# Power_onboard.net
KiCad netlist of a schematic drawn in Altium Designer
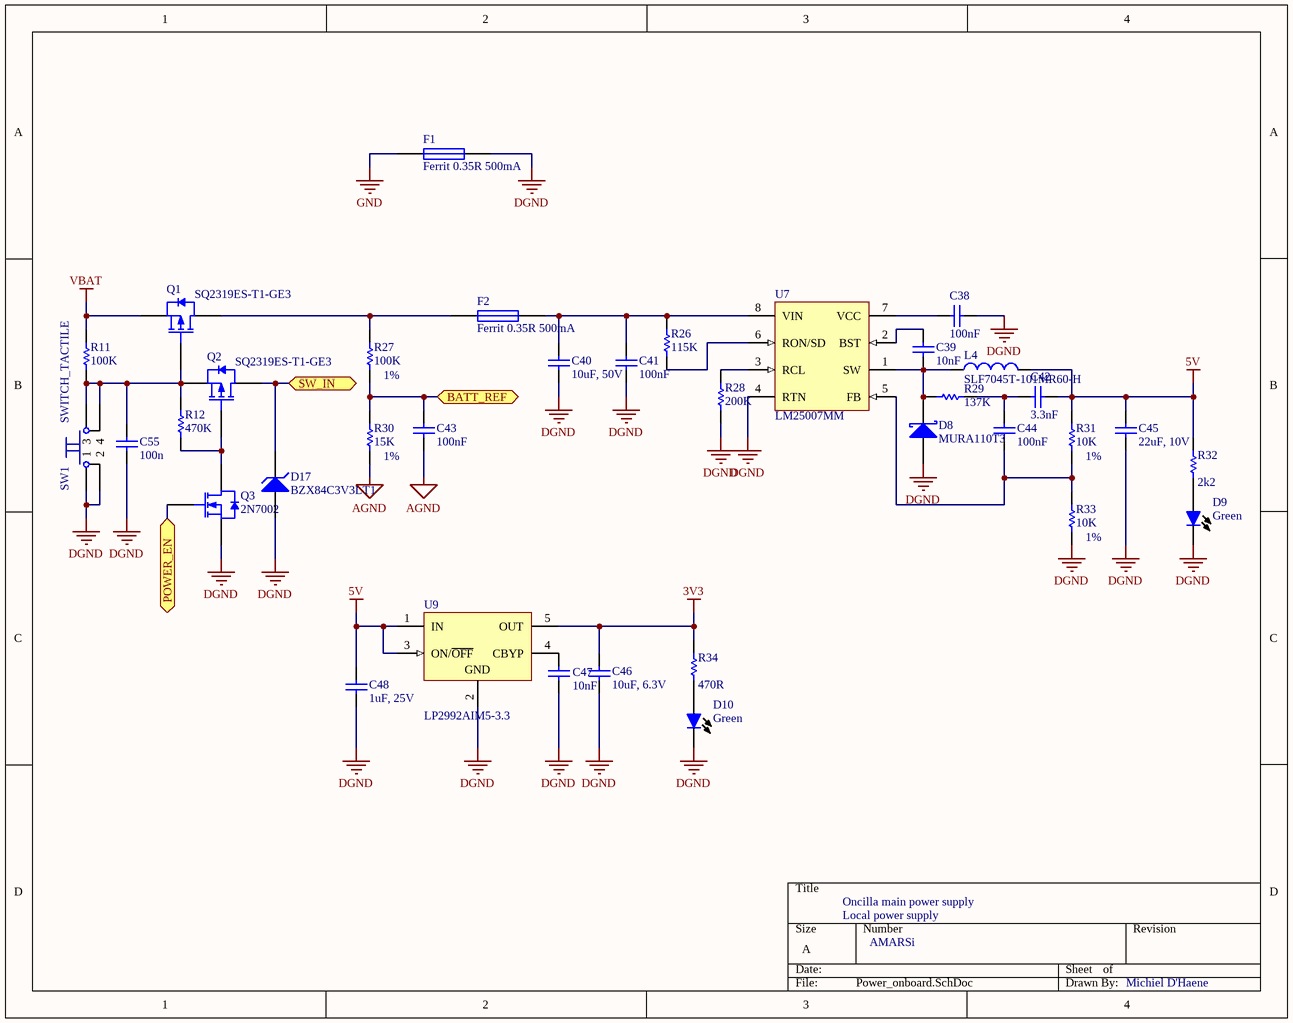
[diagram p0: Power_onboard.SchDoc]

(export (version "E")
  (design (tool "Eeschema 10.0.6"))
  (components
    (comp (ref "C38")
      (value "100nF")
      (footprint "CAPC1608L")
      (description "Capacitor (Semiconductor SIM Model)")
      (fields (field (name "PUBLISHER") "Altium Limited"))
      (libsource (lib "Miscellaneous Devices") (part "Cap Semi"))
    )
    (comp (ref "C39")
      (value "10nF")
      (footprint "CAPC1608L")
      (description "Capacitor (Semiconductor SIM Model)")
      (fields (field (name "PUBLISHER") "Altium Limited"))
      (libsource (lib "Miscellaneous Devices") (part "Cap Semi"))
    )
    (comp (ref "C40")
      (value "10uF, 50V")
      (footprint "CAPC3216L")
      (description "Capacitor (Semiconductor SIM Model)")
      (fields (field (name "PUBLISHER") "Altium Limited"))
      (libsource (lib "Miscellaneous Devices") (part "Cap Semi"))
    )
    (comp (ref "C41")
      (value "100nF")
      (footprint "CAPC1608L")
      (description "Capacitor (Semiconductor SIM Model)")
      (fields (field (name "PUBLISHER") "Altium Limited"))
      (libsource (lib "Miscellaneous Devices") (part "Cap Semi"))
    )
    (comp (ref "C42")
      (value "3.3nF")
      (footprint "CAPC1608L")
      (description "Capacitor (Semiconductor SIM Model)")
      (fields (field (name "PUBLISHER") "Altium Limited"))
      (libsource (lib "Miscellaneous Devices") (part "Cap Semi"))
    )
    (comp (ref "C43")
      (value "100nF")
      (footprint "CAPC1608L")
      (description "Capacitor (Semiconductor SIM Model)")
      (fields (field (name "PUBLISHER") "Altium Limited"))
      (libsource (lib "Miscellaneous Devices") (part "Cap Semi"))
    )
    (comp (ref "C44")
      (value "100nF")
      (footprint "CAPC1608L")
      (description "Capacitor (Semiconductor SIM Model)")
      (fields (field (name "Comment") "22nF") (field (name "PUBLISHER") "Altium Limited"))
      (libsource (lib "Miscellaneous Devices") (part "Cap Semi"))
    )
    (comp (ref "C45")
      (value "22uF, 10V")
      (footprint "CAPC3216L")
      (description "Capacitor (Semiconductor SIM Model)")
      (fields (field (name "PUBLISHER") "Altium Limited"))
      (libsource (lib "Miscellaneous Devices") (part "Cap Semi"))
    )
    (comp (ref "C46")
      (value "10uF, 6.3V")
      (footprint "CAPC1608L")
      (description "Capacitor (Semiconductor SIM Model)")
      (fields (field (name "PUBLISHER") "Altium Limited"))
      (libsource (lib "Miscellaneous Devices") (part "Cap Semi"))
    )
    (comp (ref "C47")
      (value "10nF")
      (footprint "CAPC1608L")
      (description "Capacitor (Semiconductor SIM Model)")
      (fields (field (name "PUBLISHER") "Altium Limited"))
      (libsource (lib "Miscellaneous Devices") (part "Cap Semi"))
    )
    (comp (ref "C48")
      (value "1uF, 25V")
      (footprint "CAPC1608L")
      (description "Capacitor (Semiconductor SIM Model)")
      (fields (field (name "PUBLISHER") "Altium Limited"))
      (libsource (lib "Miscellaneous Devices") (part "Cap Semi"))
    )
    (comp (ref "C55")
      (value "100n")
      (footprint "CAPC1608L")
      (description "Capacitor (Semiconductor SIM Model)")
      (fields (field (name "PUBLISHER") "Altium Limited"))
      (libsource (lib "Miscellaneous Devices") (part "Cap Semi"))
    )
    (comp (ref "D8")
      (value "MURA110T3")
      (footprint "SMA")
      (description "Schottky Rectifier")
      (fields (field (name "PUBLISHER") "Altium Limited"))
      (libsource (lib "IR Rectifier - Schottky") (part "10MQ060N"))
    )
    (comp (ref "D9")
      (value "LED Green")
      (footprint "CD1608-0603")
      (description "LED")
      (fields (field (name "COLOR") "Green"))
      (libsource (lib "Roombots") (part "LED"))
    )
    (comp (ref "D10")
      (value "LED Green")
      (footprint "CD1608-0603")
      (description "LED")
      (fields (field (name "COLOR") "Green"))
      (libsource (lib "Roombots") (part "LED"))
    )
    (comp (ref "D17")
      (value "BZX84C3V3LT1")
      (footprint "318-07")
      (description "Zener Voltage Regulator Diode")
      (fields (field (name "PUBLISHER") "Altium Limited"))
      (libsource (lib "Motorola Discrete Diode") (part "BZX84C3V3LT1"))
    )
    (comp (ref "F1")
      (value "Ferrit 0.35R 500mA")
      (footprint "RESC1608L")
      (description "Ferrit Bead")
      (fields (field (name "PUBLISHER") "Altium Limited"))
      (libsource (lib "Miscellaneous Devices") (part "Fuse 1"))
    )
    (comp (ref "F2")
      (value "Ferrit 0.35R 500mA")
      (footprint "RESC1608L")
      (description "Ferrit Bead")
      (fields (field (name "PUBLISHER") "Altium Limited"))
      (libsource (lib "Miscellaneous Devices") (part "Fuse 1"))
    )
    (comp (ref "L4")
      (value "SLF7045T-101MR60-H")
      (footprint "SLF7045T")
      (libsource (lib "New_library") (part "Inductor"))
    )
    (comp (ref "Q1")
      (value "SQ2319ES-T1-GE3")
      (footprint "SOT23_N")
      (description "P-channel Enhancement Mode Vertical D-MOSFET")
      (fields (field (name "PUBLISHER") "Altium Limited"))
      (libsource (lib "Philips Discrete MOSFET - Low Power") (part "BSS84"))
    )
    (comp (ref "Q2")
      (value "SQ2319ES-T1-GE3")
      (footprint "SOT23_N")
      (description "P-channel Enhancement Mode Vertical D-MOSFET")
      (fields (field (name "PUBLISHER") "Altium Limited"))
      (libsource (lib "Philips Discrete MOSFET - Low Power") (part "BSS84"))
    )
    (comp (ref "Q3")
      (value "2N7002")
      (footprint "SOT23_N")
      (description "N-channel Enhancement Mode Field-effect Transistor")
      (fields (field (name "PUBLISHER") "Altium Limited"))
      (libsource (lib "Philips Discrete MOSFET - Low Power") (part "BST82"))
    )
    (comp (ref "R11")
      (value "100K")
      (footprint "RESC1608L")
      (description "Semiconductor Resistor")
      (fields (field (name "Comment") "100k") (field (name "PUBLISHER") "Altium Limited"))
      (libsource (lib "Miscellaneous Devices") (part "Res Semi"))
    )
    (comp (ref "R12")
      (value "470K")
      (footprint "RESC1608L")
      (description "Semiconductor Resistor")
      (fields (field (name "Comment") "100k") (field (name "PUBLISHER") "Altium Limited"))
      (libsource (lib "Miscellaneous Devices") (part "Res Semi"))
    )
    (comp (ref "R26")
      (value "115K")
      (footprint "RESC1608L")
      (description "Semiconductor Resistor")
      (fields (field (name "Comment") "115k") (field (name "PUBLISHER") "Altium Limited"))
      (libsource (lib "Miscellaneous Devices") (part "Res Semi"))
    )
    (comp (ref "R27")
      (value "100K")
      (footprint "RESC1608L")
      (description "Semiconductor Resistor")
      (fields
        (field (name "PRECISION") "1%")
        (field (name "Comment") "100k, 1%")
        (field (name "PUBLISHER") "Altium Limited")
      )
      (libsource (lib "Miscellaneous Devices") (part "Res Semi"))
    )
    (comp (ref "R28")
      (value "200K")
      (footprint "RESC1608L")
      (description "Semiconductor Resistor")
      (fields (field (name "Comment") "200k") (field (name "PUBLISHER") "Altium Limited"))
      (libsource (lib "Miscellaneous Devices") (part "Res Semi"))
    )
    (comp (ref "R29")
      (value "137K")
      (footprint "RESC1608L")
      (description "Semiconductor Resistor")
      (fields (field (name "Comment") "138k") (field (name "PUBLISHER") "Altium Limited"))
      (libsource (lib "Miscellaneous Devices") (part "Res Semi"))
    )
    (comp (ref "R30")
      (value "15K")
      (footprint "RESC1608L")
      (description "Semiconductor Resistor")
      (fields
        (field (name "PRECISION") "1%")
        (field (name "Comment") "15k, 1%")
        (field (name "PUBLISHER") "Altium Limited")
      )
      (libsource (lib "Miscellaneous Devices") (part "Res Semi"))
    )
    (comp (ref "R31")
      (value "10K")
      (footprint "RESC1608L")
      (description "Semiconductor Resistor")
      (fields
        (field (name "PRECISION") "1%")
        (field (name "Comment") "10k, 1%")
        (field (name "PUBLISHER") "Altium Limited")
      )
      (libsource (lib "Miscellaneous Devices") (part "Res Semi"))
    )
    (comp (ref "R32")
      (value "2k2")
      (footprint "RESC1608L")
      (description "Semiconductor Resistor")
      (fields (field (name "PUBLISHER") "Altium Limited"))
      (libsource (lib "Miscellaneous Devices") (part "Res Semi"))
    )
    (comp (ref "R33")
      (value "10K")
      (footprint "RESC1608L")
      (description "Semiconductor Resistor")
      (fields
        (field (name "PRECISION") "1%")
        (field (name "Comment") "10k, 1%")
        (field (name "PUBLISHER") "Altium Limited")
      )
      (libsource (lib "Miscellaneous Devices") (part "Res Semi"))
    )
    (comp (ref "R34")
      (value "470R")
      (footprint "RESC1608L")
      (description "Semiconductor Resistor")
      (fields (field (name "PUBLISHER") "Altium Limited"))
      (libsource (lib "Miscellaneous Devices") (part "Res Semi"))
    )
    (comp (ref "SW1")
      (value "SWITCH_TACTILE")
      (footprint "TACTILE_SWITCH")
      (libsource (lib "New_library") (part "SWITCH_TACTILE"))
    )
    (comp (ref "U7")
      (value "LM25007MM")
      (footprint "MUA08A_N")
      (description "42V, 0.5A Step-Down Switching Regulator")
      (fields
        (field (name "MANUFACTURER") "National Semiconductor")
        (field (name "DIGIKEYPARTNUMBER") "LM25007MMCT-ND")
        (field (name "PUBLISHER") "Altium Limited")
      )
      (libsource (lib "NSC MiscPower") (part "LM25007MM"))
    )
    (comp (ref "U9")
      (value "LP2992AIM5-3.3")
      (footprint "MF05A_N")
      (description "Micropower 250 mA Low-Noise Ultra Low-Dropout Regulator in SOT-23 and LLP Packages")
      (fields
        (field (name "PARTNUMBER") "LP2992AIM5-5.0")
        (field (name "MANUFACTURER") "National Semiconductor")
        (field (name "PUBLISHER") "Altium Limited")
      )
      (libsource (lib "NSC LDO") (part "LP2992AIM5-5.0"))
    )
  )
  (nets
    (net (code "1") (name "/BATT_REF") (class "Default")
      (node (ref "C43") (pin "2") (pinfunction "2_2") (pintype "passive"))
      (node (ref "R27") (pin "1") (pinfunction "1_1") (pintype "passive"))
      (node (ref "R30") (pin "2") (pinfunction "2_2") (pintype "passive"))
    )
    (net (code "2") (name "/POWER_EN") (class "Default")
      (node (ref "Q3") (pin "1") (pinfunction "G_1") (pintype "passive"))
    )
    (net (code "3") (name "/SW_IN") (class "Default")
      (node (ref "D17") (pin "3") (pinfunction "K_3") (pintype "passive"))
      (node (ref "Q2") (pin "3") (pinfunction "D_3") (pintype "passive"))
    )
    (net (code "4") (name "3V3") (class "Default")
      (node (ref "C46") (pin "2") (pinfunction "2_2") (pintype "passive"))
      (node (ref "R34") (pin "2") (pinfunction "2_2") (pintype "passive"))
      (node (ref "U9") (pin "5") (pinfunction "OUT_5") (pintype "power_in"))
    )
    (net (code "5") (name "5V") (class "Default")
      (node (ref "C42") (pin "2") (pinfunction "2_2") (pintype "passive"))
      (node (ref "C45") (pin "2") (pinfunction "2_2") (pintype "passive"))
      (node (ref "C48") (pin "2") (pinfunction "2_2") (pintype "passive"))
      (node (ref "L4") (pin "2") (pinfunction "2_2") (pintype "passive"))
      (node (ref "R31") (pin "2") (pinfunction "2_2") (pintype "passive"))
      (node (ref "R32") (pin "2") (pinfunction "2_2") (pintype "passive"))
      (node (ref "U9") (pin "1") (pinfunction "IN_1") (pintype "power_in"))
      (node (ref "U9") (pin "3") (pinfunction "ON/~{OFF}_3") (pintype "input"))
    )
    (net (code "6") (name "AGND") (class "Default")
      (node (ref "C43") (pin "1") (pinfunction "1_1") (pintype "passive"))
      (node (ref "R30") (pin "1") (pinfunction "1_1") (pintype "passive"))
    )
    (net (code "7") (name "DGND") (class "Default")
      (node (ref "C38") (pin "1") (pinfunction "1_1") (pintype "passive"))
      (node (ref "C40") (pin "1") (pinfunction "1_1") (pintype "passive"))
      (node (ref "C41") (pin "1") (pinfunction "1_1") (pintype "passive"))
      (node (ref "C45") (pin "1") (pinfunction "1_1") (pintype "passive"))
      (node (ref "C46") (pin "1") (pinfunction "1_1") (pintype "passive"))
      (node (ref "C47") (pin "1") (pinfunction "1_1") (pintype "passive"))
      (node (ref "C48") (pin "1") (pinfunction "1_1") (pintype "passive"))
      (node (ref "C55") (pin "1") (pinfunction "1_1") (pintype "passive"))
      (node (ref "D10") (pin "2") (pinfunction "C_2") (pintype "passive"))
      (node (ref "D17") (pin "1") (pinfunction "A_1") (pintype "passive"))
      (node (ref "D8") (pin "1") (pinfunction "A_1") (pintype "passive"))
      (node (ref "D9") (pin "2") (pinfunction "C_2") (pintype "passive"))
      (node (ref "F1") (pin "2") (pinfunction "2_2") (pintype "passive"))
      (node (ref "Q3") (pin "2") (pinfunction "S_2") (pintype "passive"))
      (node (ref "R28") (pin "1") (pinfunction "1_1") (pintype "passive"))
      (node (ref "R33") (pin "1") (pinfunction "1_1") (pintype "passive"))
      (node (ref "SW1") (pin "1") (pinfunction "1_1") (pintype "passive"))
      (node (ref "SW1") (pin "2") (pinfunction "2_2") (pintype "passive"))
      (node (ref "U7") (pin "4") (pinfunction "RTN_4") (pintype "power_in"))
      (node (ref "U9") (pin "2") (pinfunction "GND_2") (pintype "power_in"))
    )
    (net (code "8") (name "GND") (class "Default")
      (node (ref "F1") (pin "1") (pinfunction "1_1") (pintype "passive"))
    )
    (net (code "9") (name "Net-(C42-Pad1)") (class "Default")
      (node (ref "C42") (pin "1") (pinfunction "1_1") (pintype "passive"))
      (node (ref "C44") (pin "2") (pinfunction "2_2") (pintype "passive"))
      (node (ref "R29") (pin "1") (pinfunction "1_1") (pintype "passive"))
    )
    (net (code "10") (name "Net-(D8-K)") (class "Default")
      (node (ref "C39") (pin "1") (pinfunction "1_1") (pintype "passive"))
      (node (ref "D8") (pin "2") (pinfunction "K_2") (pintype "passive"))
      (node (ref "L4") (pin "1") (pinfunction "1_1") (pintype "passive"))
      (node (ref "R29") (pin "2") (pinfunction "2_2") (pintype "passive"))
      (node (ref "U7") (pin "1") (pinfunction "SW_1") (pintype "power_in"))
    )
    (net (code "11") (name "Net-(D9-A)") (class "Default")
      (node (ref "D9") (pin "1") (pinfunction "A_1") (pintype "passive"))
      (node (ref "R32") (pin "1") (pinfunction "1_1") (pintype "passive"))
    )
    (net (code "12") (name "Net-(D10-A)") (class "Default")
      (node (ref "D10") (pin "1") (pinfunction "A_1") (pintype "passive"))
      (node (ref "R34") (pin "1") (pinfunction "1_1") (pintype "passive"))
    )
    (net (code "13") (name "Net-(Q1-D)") (class "Default")
      (node (ref "F2") (pin "1") (pinfunction "1_1") (pintype "passive"))
      (node (ref "Q1") (pin "3") (pinfunction "D_3") (pintype "passive"))
      (node (ref "R27") (pin "2") (pinfunction "2_2") (pintype "passive"))
    )
    (net (code "14") (name "Net-(Q1-G)") (class "Default")
      (node (ref "C55") (pin "2") (pinfunction "2_2") (pintype "passive"))
      (node (ref "Q1") (pin "1") (pinfunction "G_1") (pintype "passive"))
      (node (ref "Q2") (pin "2") (pinfunction "S_2") (pintype "passive"))
      (node (ref "R11") (pin "1") (pinfunction "1_1") (pintype "passive"))
      (node (ref "R12") (pin "2") (pinfunction "2_2") (pintype "passive"))
      (node (ref "SW1") (pin "3") (pinfunction "3_3") (pintype "passive"))
      (node (ref "SW1") (pin "4") (pinfunction "4_4") (pintype "passive"))
    )
    (net (code "15") (name "Net-(Q2-G)") (class "Default")
      (node (ref "Q2") (pin "1") (pinfunction "G_1") (pintype "passive"))
      (node (ref "Q3") (pin "3") (pinfunction "D_3") (pintype "passive"))
      (node (ref "R12") (pin "1") (pinfunction "1_1") (pintype "passive"))
    )
    (net (code "16") (name "Net-(U7-BST)") (class "Default")
      (node (ref "C39") (pin "2") (pinfunction "2_2") (pintype "passive"))
      (node (ref "U7") (pin "2") (pinfunction "BST_2") (pintype "input"))
    )
    (net (code "17") (name "Net-(U7-FB)") (class "Default")
      (node (ref "C44") (pin "1") (pinfunction "1_1") (pintype "passive"))
      (node (ref "R31") (pin "1") (pinfunction "1_1") (pintype "passive"))
      (node (ref "R33") (pin "2") (pinfunction "2_2") (pintype "passive"))
      (node (ref "U7") (pin "5") (pinfunction "FB_5") (pintype "input"))
    )
    (net (code "18") (name "Net-(U7-RCL)") (class "Default")
      (node (ref "R28") (pin "2") (pinfunction "2_2") (pintype "passive"))
      (node (ref "U7") (pin "3") (pinfunction "RCL_3") (pintype "input"))
    )
    (net (code "19") (name "Net-(U7-RON{slash}SD)") (class "Default")
      (node (ref "R26") (pin "1") (pinfunction "1_1") (pintype "passive"))
      (node (ref "U7") (pin "6") (pinfunction "RON/SD_6") (pintype "input"))
    )
    (net (code "20") (name "Net-(U7-VCC)") (class "Default")
      (node (ref "C38") (pin "2") (pinfunction "2_2") (pintype "passive"))
      (node (ref "U7") (pin "7") (pinfunction "VCC_7") (pintype "power_in"))
    )
    (net (code "21") (name "Net-(U7-VIN)") (class "Default")
      (node (ref "C40") (pin "2") (pinfunction "2_2") (pintype "passive"))
      (node (ref "C41") (pin "2") (pinfunction "2_2") (pintype "passive"))
      (node (ref "F2") (pin "2") (pinfunction "2_2") (pintype "passive"))
      (node (ref "R26") (pin "2") (pinfunction "2_2") (pintype "passive"))
      (node (ref "U7") (pin "8") (pinfunction "VIN_8") (pintype "power_in"))
    )
    (net (code "22") (name "Net-(U9-CBYP)") (class "Default")
      (node (ref "C47") (pin "2") (pinfunction "2_2") (pintype "passive"))
      (node (ref "U9") (pin "4") (pinfunction "CBYP_4") (pintype "passive"))
    )
    (net (code "23") (name "VBAT") (class "Default")
      (node (ref "Q1") (pin "2") (pinfunction "S_2") (pintype "passive"))
      (node (ref "R11") (pin "2") (pinfunction "2_2") (pintype "passive"))
    )
  )
)
